# arduinoDra818.net
KiCad netlist of a schematic drawn in EAGLE
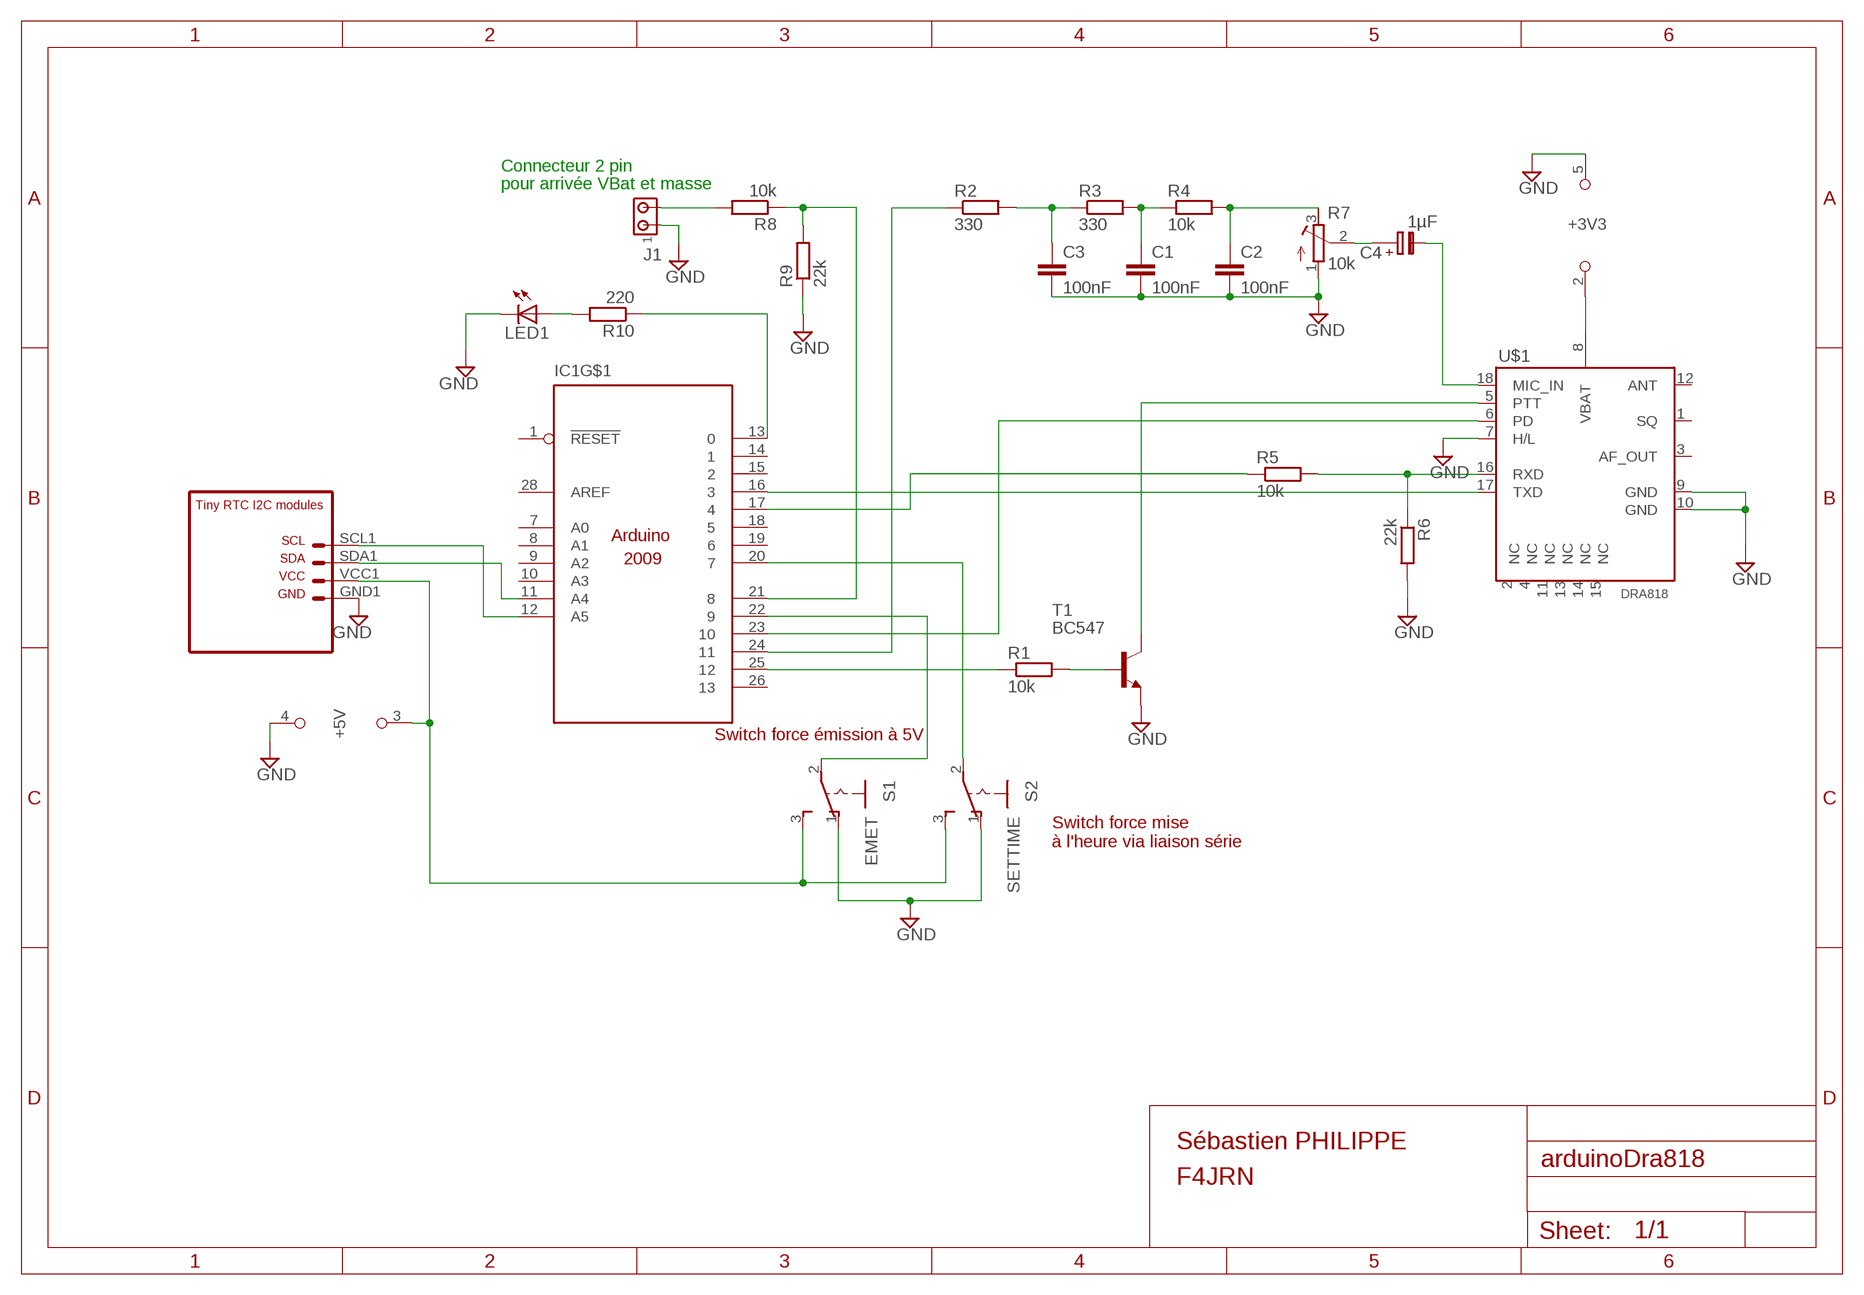
[diagram p0: schematic, sheet 1]

(export (version "E")
  (design (tool "Eeschema 10.0.6"))
  (components
    (comp (ref "C1")
      (value "100nF")
      (footprint "eagle-import:C050-025X075")
      (libsource (lib "eagle-import") (part "C-EU050-025X075"))
    )
    (comp (ref "C2")
      (value "100nF")
      (footprint "eagle-import:C050-025X075")
      (libsource (lib "eagle-import") (part "C-EU050-025X075"))
    )
    (comp (ref "C3")
      (value "100nF")
      (footprint "eagle-import:C050-025X075")
      (libsource (lib "eagle-import") (part "C-EU050-025X075"))
    )
    (comp (ref "C4")
      (value "1µF")
      (footprint "eagle-import:E2,0-5")
      (libsource (lib "eagle-import") (part "C-PR-2,0X5"))
    )
    (comp (ref "IC1")
      (value "Arduino")
      (footprint "eagle-import:ARDUINO2009_1")
      (libsource (lib "eagle-import") (part "ARDUINO2009_21"))
    )
    (comp (ref "J1")
      (value "MTA02-100")
      (footprint "eagle-import:10X02MTA")
      (libsource (lib "eagle-import") (part "MTA02-100"))
    )
    (comp (ref "LED1")
      (value "LED3MM")
      (footprint "eagle-import:LED3MM")
      (libsource (lib "eagle-import") (part "LED3MM"))
    )
    (comp (ref "R1")
      (value "10k")
      (footprint "eagle-import:0411_15")
      (libsource (lib "eagle-import") (part "R-EU_0411/15"))
    )
    (comp (ref "R2")
      (value "330")
      (footprint "eagle-import:0411_15")
      (libsource (lib "eagle-import") (part "R-EU_0411/15"))
    )
    (comp (ref "R3")
      (value "330")
      (footprint "eagle-import:0411_15")
      (libsource (lib "eagle-import") (part "R-EU_0411/15"))
    )
    (comp (ref "R4")
      (value "10k")
      (footprint "eagle-import:0411_15")
      (libsource (lib "eagle-import") (part "R-EU_0411/15"))
    )
    (comp (ref "R5")
      (value "10k")
      (footprint "eagle-import:0411_15")
      (libsource (lib "eagle-import") (part "R-EU_0411/15"))
    )
    (comp (ref "R6")
      (value "22k")
      (footprint "eagle-import:0411_15")
      (libsource (lib "eagle-import") (part "R-EU_0411/15"))
    )
    (comp (ref "R7")
      (value "10k")
      (footprint "eagle-import:RTRIM3339P")
      (libsource (lib "eagle-import") (part "R-TRIMM3339P"))
    )
    (comp (ref "R8")
      (value "10k")
      (footprint "eagle-import:0411_15")
      (libsource (lib "eagle-import") (part "R-EU_0411/15"))
    )
    (comp (ref "R9")
      (value "22k")
      (footprint "eagle-import:0411_15")
      (libsource (lib "eagle-import") (part "R-EU_0411/15"))
    )
    (comp (ref "R10")
      (value "220")
      (footprint "eagle-import:0411_15")
      (libsource (lib "eagle-import") (part "R-EU_0411/15"))
    )
    (comp (ref "S1")
      (value "EMET")
      (footprint "eagle-import:255SB")
      (libsource (lib "eagle-import") (part "255SB"))
    )
    (comp (ref "S2")
      (value "SETTIME")
      (footprint "eagle-import:255SB")
      (libsource (lib "eagle-import") (part "255SB"))
    )
    (comp (ref "T1")
      (value "BC547")
      (footprint "eagle-import:TO92")
      (libsource (lib "eagle-import") (part "BC547"))
    )
    (comp (ref "U$1")
      (value "DRA818")
      (footprint "eagle-import:DRA818A")
      (libsource (lib "eagle-import") (part "DRA818A"))
    )
    (comp (ref "U$2")
      (value "RTC")
      (footprint "eagle-import:RTC")
      (libsource (lib "eagle-import") (part "RTC"))
    )
  )
  (nets
    (net (code "1") (name "GND") (class "Default")
      (node (ref "C1") (pin "2") (pinfunction "2_2") (pintype "passive"))
      (node (ref "C2") (pin "2") (pinfunction "2_2") (pintype "passive"))
      (node (ref "C3") (pin "2") (pinfunction "2_2") (pintype "passive"))
      (node (ref "IC1") (pin "4") (pinfunction "GND_4") (pintype "power_in"))
      (node (ref "IC1") (pin "5") (pinfunction "GND_5") (pintype "power_in"))
      (node (ref "J1") (pin "1") (pinfunction "1_1") (pintype "passive"))
      (node (ref "LED1") (pin "K") (pinfunction "C_K") (pintype "passive"))
      (node (ref "R6") (pin "2") (pinfunction "2_2") (pintype "passive"))
      (node (ref "R7") (pin "1") (pinfunction "E_1") (pintype "passive"))
      (node (ref "R9") (pin "1") (pinfunction "1_1") (pintype "passive"))
      (node (ref "S1") (pin "1") (pinfunction "O_1") (pintype "passive"))
      (node (ref "S2") (pin "1") (pinfunction "O_1") (pintype "passive"))
      (node (ref "T1") (pin "1") (pinfunction "E_1") (pintype "passive"))
      (node (ref "U$1") (pin "10") (pinfunction "GND_10") (pintype "bidirectional"))
      (node (ref "U$1") (pin "7") (pinfunction "H/L_7") (pintype "bidirectional"))
      (node (ref "U$1") (pin "9") (pinfunction "GND_9") (pintype "bidirectional"))
      (node (ref "U$2") (pin "GND1") (pinfunction "GND1_GND1") (pintype "passive"))
    )
    (net (code "2") (name "Net-(C1-Pad1)") (class "Default")
      (node (ref "C1") (pin "1") (pinfunction "1_1") (pintype "passive"))
      (node (ref "R3") (pin "2") (pinfunction "2_2") (pintype "passive"))
      (node (ref "R4") (pin "1") (pinfunction "1_1") (pintype "passive"))
    )
    (net (code "3") (name "Net-(C3-Pad1)") (class "Default")
      (node (ref "C3") (pin "1") (pinfunction "1_1") (pintype "passive"))
      (node (ref "R2") (pin "2") (pinfunction "2_2") (pintype "passive"))
      (node (ref "R3") (pin "1") (pinfunction "1_1") (pintype "passive"))
    )
    (net (code "4") (name "Net-(IC1A-0)") (class "Default")
      (node (ref "IC1") (pin "13") (pinfunction "0_13") (pintype "bidirectional"))
      (node (ref "R10") (pin "1") (pinfunction "1_1") (pintype "passive"))
    )
    (net (code "5") (name "Net-(IC1A-3)") (class "Default")
      (node (ref "IC1") (pin "16") (pinfunction "3_16") (pintype "bidirectional"))
      (node (ref "U$1") (pin "17") (pinfunction "TXD_17") (pintype "bidirectional"))
    )
    (net (code "6") (name "Net-(IC1A-4)") (class "Default")
      (node (ref "IC1") (pin "17") (pinfunction "4_17") (pintype "bidirectional"))
      (node (ref "R5") (pin "1") (pinfunction "1_1") (pintype "passive"))
    )
    (net (code "7") (name "Net-(IC1A-7)") (class "Default")
      (node (ref "IC1") (pin "20") (pinfunction "7_20") (pintype "bidirectional"))
      (node (ref "S2") (pin "2") (pinfunction "P_2") (pintype "passive"))
    )
    (net (code "8") (name "Net-(IC1A-8)") (class "Default")
      (node (ref "IC1") (pin "21") (pinfunction "8_21") (pintype "bidirectional"))
      (node (ref "R8") (pin "1") (pinfunction "1_1") (pintype "passive"))
      (node (ref "R9") (pin "2") (pinfunction "2_2") (pintype "passive"))
    )
    (net (code "9") (name "Net-(IC1A-9)") (class "Default")
      (node (ref "IC1") (pin "22") (pinfunction "9_22") (pintype "bidirectional"))
      (node (ref "S1") (pin "2") (pinfunction "P_2") (pintype "passive"))
    )
    (net (code "10") (name "Net-(IC1A-10)") (class "Default")
      (node (ref "IC1") (pin "23") (pinfunction "10_23") (pintype "bidirectional"))
      (node (ref "U$1") (pin "6") (pinfunction "PD_6") (pintype "bidirectional"))
    )
    (net (code "11") (name "Net-(IC1A-11)") (class "Default")
      (node (ref "IC1") (pin "24") (pinfunction "11_24") (pintype "bidirectional"))
      (node (ref "R2") (pin "1") (pinfunction "1_1") (pintype "passive"))
    )
    (net (code "12") (name "Net-(IC1A-12)") (class "Default")
      (node (ref "IC1") (pin "25") (pinfunction "12_25") (pintype "bidirectional"))
      (node (ref "R1") (pin "1") (pinfunction "1_1") (pintype "passive"))
    )
    (net (code "13") (name "Net-(IC1A-A4)") (class "Default")
      (node (ref "IC1") (pin "11") (pinfunction "A4_11") (pintype "bidirectional"))
      (node (ref "U$2") (pin "SDA1") (pinfunction "SDA1_SDA1") (pintype "passive"))
    )
    (net (code "14") (name "Net-(IC1A-A5)") (class "Default")
      (node (ref "IC1") (pin "12") (pinfunction "A5_12") (pintype "bidirectional"))
      (node (ref "U$2") (pin "SCL1") (pinfunction "SCL1_SCL1") (pintype "passive"))
    )
    (net (code "15") (name "Net-(IC1B-+5V)") (class "Default")
      (node (ref "IC1") (pin "3") (pinfunction "+5V_3") (pintype "power_in"))
      (node (ref "S1") (pin "3") (pinfunction "S_3") (pintype "passive"))
      (node (ref "S2") (pin "3") (pinfunction "S_3") (pintype "passive"))
      (node (ref "U$2") (pin "VCC1") (pinfunction "VCC1_VCC1") (pintype "passive"))
    )
    (net (code "16") (name "Net-(IC1C-+3V3)") (class "Default")
      (node (ref "IC1") (pin "2") (pinfunction "+3V3_2") (pintype "power_in"))
      (node (ref "U$1") (pin "8") (pinfunction "VBAT_8") (pintype "bidirectional"))
    )
    (net (code "17") (name "Net-(J1-Pad2)") (class "Default")
      (node (ref "J1") (pin "2") (pinfunction "2_2") (pintype "passive"))
      (node (ref "R8") (pin "2") (pinfunction "2_2") (pintype "passive"))
    )
    (net (code "18") (name "Net-(LED1-PadA)") (class "Default")
      (node (ref "LED1") (pin "A") (pinfunction "A_A") (pintype "passive"))
      (node (ref "R10") (pin "2") (pinfunction "2_2") (pintype "passive"))
    )
    (net (code "19") (name "Net-(R7-A)") (class "Default")
      (node (ref "C2") (pin "1") (pinfunction "1_1") (pintype "passive"))
      (node (ref "R4") (pin "2") (pinfunction "2_2") (pintype "passive"))
      (node (ref "R7") (pin "3") (pinfunction "A_3") (pintype "passive"))
    )
    (net (code "20") (name "Net-(R7-S)") (class "Default")
      (node (ref "C4") (pin "+") (pinfunction "+_+") (pintype "passive"))
      (node (ref "R7") (pin "2") (pinfunction "S_2") (pintype "passive"))
    )
    (net (code "21") (name "Net-(T1-B)") (class "Default")
      (node (ref "R1") (pin "2") (pinfunction "2_2") (pintype "passive"))
      (node (ref "T1") (pin "2") (pinfunction "B_2") (pintype "passive"))
    )
    (net (code "22") (name "Net-(T1-C)") (class "Default")
      (node (ref "T1") (pin "3") (pinfunction "C_3") (pintype "passive"))
      (node (ref "U$1") (pin "5") (pinfunction "PTT_5") (pintype "bidirectional"))
    )
    (net (code "23") (name "Net-(U$1-MIC_IN)") (class "Default")
      (node (ref "C4") (pin "-") (pinfunction "-_-") (pintype "passive"))
      (node (ref "U$1") (pin "18") (pinfunction "MIC_IN_18") (pintype "bidirectional"))
    )
    (net (code "24") (name "Net-(U$1-RXD)") (class "Default")
      (node (ref "R5") (pin "2") (pinfunction "2_2") (pintype "passive"))
      (node (ref "R6") (pin "1") (pinfunction "1_1") (pintype "passive"))
      (node (ref "U$1") (pin "16") (pinfunction "RXD_16") (pintype "bidirectional"))
    )
    (net (code "25") (name "unconnected-(IC1A-1-Pad14)") (class "Default")
      (node (ref "IC1") (pin "14") (pinfunction "1_14") (pintype "bidirectional"))
    )
    (net (code "26") (name "unconnected-(IC1A-2-Pad15)") (class "Default")
      (node (ref "IC1") (pin "15") (pinfunction "2_15") (pintype "bidirectional"))
    )
    (net (code "27") (name "unconnected-(IC1A-5-Pad18)") (class "Default")
      (node (ref "IC1") (pin "18") (pinfunction "5_18") (pintype "bidirectional"))
    )
    (net (code "28") (name "unconnected-(IC1A-6-Pad19)") (class "Default")
      (node (ref "IC1") (pin "19") (pinfunction "6_19") (pintype "bidirectional"))
    )
    (net (code "29") (name "unconnected-(IC1A-13-Pad26)") (class "Default")
      (node (ref "IC1") (pin "26") (pinfunction "13_26") (pintype "bidirectional"))
    )
    (net (code "30") (name "unconnected-(IC1A-A0-Pad7)") (class "Default")
      (node (ref "IC1") (pin "7") (pinfunction "A0_7") (pintype "bidirectional"))
    )
    (net (code "31") (name "unconnected-(IC1A-A1-Pad8)") (class "Default")
      (node (ref "IC1") (pin "8") (pinfunction "A1_8") (pintype "bidirectional"))
    )
    (net (code "32") (name "unconnected-(IC1A-A2-Pad9)") (class "Default")
      (node (ref "IC1") (pin "9") (pinfunction "A2_9") (pintype "bidirectional"))
    )
    (net (code "33") (name "unconnected-(IC1A-A3-Pad10)") (class "Default")
      (node (ref "IC1") (pin "10") (pinfunction "A3_10") (pintype "bidirectional"))
    )
    (net (code "34") (name "unconnected-(IC1A-AREF-Pad28)") (class "Default")
      (node (ref "IC1") (pin "28") (pinfunction "AREF_28") (pintype "bidirectional"))
    )
    (net (code "35") (name "unconnected-(IC1A-~{RESET}-Pad1)") (class "Default")
      (node (ref "IC1") (pin "1") (pinfunction "~{RESET}_1") (pintype "bidirectional"))
    )
    (net (code "36") (name "unconnected-(U$1-AF_OUT-Pad3)") (class "Default")
      (node (ref "U$1") (pin "3") (pinfunction "AF_OUT_3") (pintype "bidirectional"))
    )
    (net (code "37") (name "unconnected-(U$1-ANT-Pad12)") (class "Default")
      (node (ref "U$1") (pin "12") (pinfunction "ANT_12") (pintype "bidirectional"))
    )
    (net (code "38") (name "unconnected-(U$1-NC-Pad2)") (class "Default")
      (node (ref "U$1") (pin "2") (pinfunction "NC_2") (pintype "bidirectional"))
    )
    (net (code "39") (name "unconnected-(U$1-NC-Pad4)") (class "Default")
      (node (ref "U$1") (pin "4") (pinfunction "NC_4") (pintype "bidirectional"))
    )
    (net (code "40") (name "unconnected-(U$1-NC-Pad11)") (class "Default")
      (node (ref "U$1") (pin "11") (pinfunction "NC_11") (pintype "bidirectional"))
    )
    (net (code "41") (name "unconnected-(U$1-NC-Pad13)") (class "Default")
      (node (ref "U$1") (pin "13") (pinfunction "NC_13") (pintype "bidirectional"))
    )
    (net (code "42") (name "unconnected-(U$1-NC-Pad14)") (class "Default")
      (node (ref "U$1") (pin "14") (pinfunction "NC_14") (pintype "bidirectional"))
    )
    (net (code "43") (name "unconnected-(U$1-NC-Pad15)") (class "Default")
      (node (ref "U$1") (pin "15") (pinfunction "NC_15") (pintype "bidirectional"))
    )
    (net (code "44") (name "unconnected-(U$1-SQ-Pad1)") (class "Default")
      (node (ref "U$1") (pin "1") (pinfunction "SQ_1") (pintype "bidirectional"))
    )
  )
)
